# Remote_sensor.net
KiCad netlist of a schematic drawn in Altium Designer
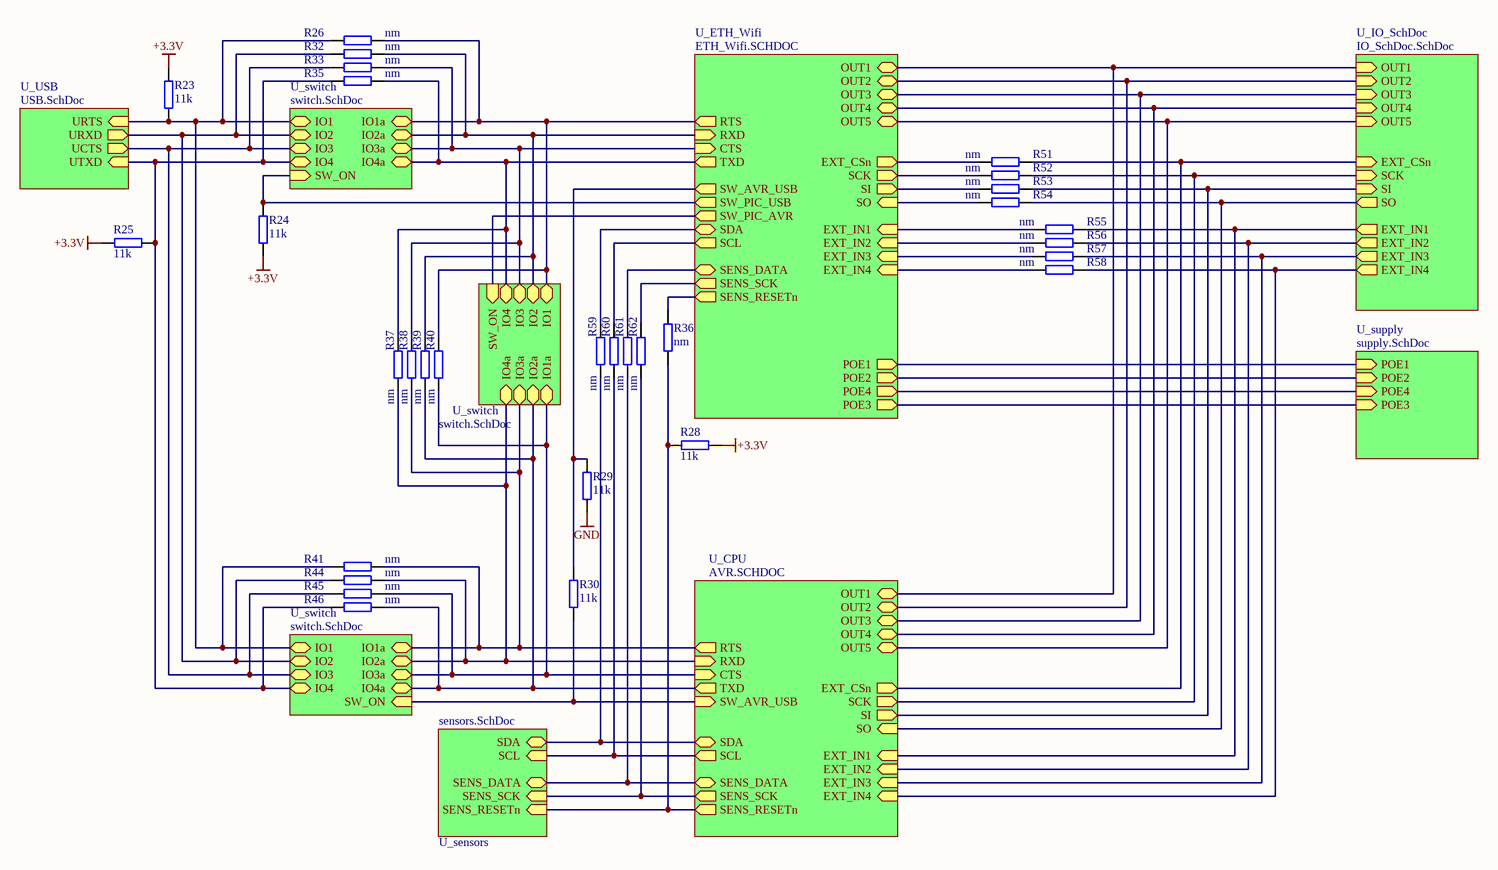
[diagram p0: Remote_sensor.SCHDOC]

(export (version "E")
  (design (tool "Eeschema 10.0.6"))
  (components
    (comp (ref "R23")
      (value "11k")
      (footprint "0603")
      (description "SMD Resistor")
      (libsource (lib "LIBRARY_SCH") (part "RES_SMD"))
    )
    (comp (ref "R24")
      (value "11k")
      (footprint "0603")
      (description "SMD Resistor")
      (libsource (lib "LIBRARY_SCH") (part "RES_SMD"))
    )
    (comp (ref "R25")
      (value "11k")
      (footprint "0603")
      (description "SMD Resistor")
      (libsource (lib "LIBRARY_SCH") (part "RES_SMD"))
    )
    (comp (ref "R26")
      (value "nm")
      (footprint "0603")
      (description "SMD Resistor")
      (libsource (lib "LIBRARY_SCH") (part "RES_SMD"))
    )
    (comp (ref "R28")
      (value "11k")
      (footprint "0603")
      (description "SMD Resistor")
      (libsource (lib "LIBRARY_SCH") (part "RES_SMD"))
    )
    (comp (ref "R29")
      (value "11k")
      (footprint "0603")
      (description "SMD Resistor")
      (libsource (lib "LIBRARY_SCH") (part "RES_SMD"))
    )
    (comp (ref "R30")
      (value "11k")
      (footprint "0603")
      (description "SMD Resistor")
      (libsource (lib "LIBRARY_SCH") (part "RES_SMD"))
    )
    (comp (ref "R32")
      (value "nm")
      (footprint "0603")
      (description "SMD Resistor")
      (libsource (lib "LIBRARY_SCH") (part "RES_SMD"))
    )
    (comp (ref "R33")
      (value "nm")
      (footprint "0603")
      (description "SMD Resistor")
      (libsource (lib "LIBRARY_SCH") (part "RES_SMD"))
    )
    (comp (ref "R35")
      (value "nm")
      (footprint "0603")
      (description "SMD Resistor")
      (libsource (lib "LIBRARY_SCH") (part "RES_SMD"))
    )
    (comp (ref "R36")
      (value "nm")
      (footprint "0603")
      (description "SMD Resistor")
      (libsource (lib "LIBRARY_SCH") (part "RES_SMD"))
    )
    (comp (ref "R37")
      (value "nm")
      (footprint "0603")
      (description "SMD Resistor")
      (libsource (lib "LIBRARY_SCH") (part "RES_SMD"))
    )
    (comp (ref "R38")
      (value "nm")
      (footprint "0603")
      (description "SMD Resistor")
      (libsource (lib "LIBRARY_SCH") (part "RES_SMD"))
    )
    (comp (ref "R39")
      (value "nm")
      (footprint "0603")
      (description "SMD Resistor")
      (libsource (lib "LIBRARY_SCH") (part "RES_SMD"))
    )
    (comp (ref "R40")
      (value "nm")
      (footprint "0603")
      (description "SMD Resistor")
      (libsource (lib "LIBRARY_SCH") (part "RES_SMD"))
    )
    (comp (ref "R41")
      (value "nm")
      (footprint "0603")
      (description "SMD Resistor")
      (libsource (lib "LIBRARY_SCH") (part "RES_SMD"))
    )
    (comp (ref "R44")
      (value "nm")
      (footprint "0603")
      (description "SMD Resistor")
      (libsource (lib "LIBRARY_SCH") (part "RES_SMD"))
    )
    (comp (ref "R45")
      (value "nm")
      (footprint "0603")
      (description "SMD Resistor")
      (libsource (lib "LIBRARY_SCH") (part "RES_SMD"))
    )
    (comp (ref "R46")
      (value "nm")
      (footprint "0603")
      (description "SMD Resistor")
      (libsource (lib "LIBRARY_SCH") (part "RES_SMD"))
    )
    (comp (ref "R51")
      (value "nm")
      (footprint "0603")
      (description "SMD Resistor")
      (libsource (lib "LIBRARY_SCH") (part "RES_SMD"))
    )
    (comp (ref "R52")
      (value "nm")
      (footprint "0603")
      (description "SMD Resistor")
      (libsource (lib "LIBRARY_SCH") (part "RES_SMD"))
    )
    (comp (ref "R53")
      (value "nm")
      (footprint "0603")
      (description "SMD Resistor")
      (libsource (lib "LIBRARY_SCH") (part "RES_SMD"))
    )
    (comp (ref "R54")
      (value "nm")
      (footprint "0603")
      (description "SMD Resistor")
      (libsource (lib "LIBRARY_SCH") (part "RES_SMD"))
    )
    (comp (ref "R55")
      (value "nm")
      (footprint "0603")
      (description "SMD Resistor")
      (libsource (lib "LIBRARY_SCH") (part "RES_SMD"))
    )
    (comp (ref "R56")
      (value "nm")
      (footprint "0603")
      (description "SMD Resistor")
      (libsource (lib "LIBRARY_SCH") (part "RES_SMD"))
    )
    (comp (ref "R57")
      (value "nm")
      (footprint "0603")
      (description "SMD Resistor")
      (libsource (lib "LIBRARY_SCH") (part "RES_SMD"))
    )
    (comp (ref "R58")
      (value "nm")
      (footprint "0603")
      (description "SMD Resistor")
      (libsource (lib "LIBRARY_SCH") (part "RES_SMD"))
    )
    (comp (ref "R59")
      (value "nm")
      (footprint "0603")
      (description "SMD Resistor")
      (libsource (lib "LIBRARY_SCH") (part "RES_SMD"))
    )
    (comp (ref "R60")
      (value "nm")
      (footprint "0603")
      (description "SMD Resistor")
      (libsource (lib "LIBRARY_SCH") (part "RES_SMD"))
    )
    (comp (ref "R61")
      (value "nm")
      (footprint "0603")
      (description "SMD Resistor")
      (libsource (lib "LIBRARY_SCH") (part "RES_SMD"))
    )
    (comp (ref "R62")
      (value "nm")
      (footprint "0603")
      (description "SMD Resistor")
      (libsource (lib "LIBRARY_SCH") (part "RES_SMD"))
    )
  )
  (nets
    (net (code "1") (name "+3.3V") (class "Default")
      (node (ref "R23") (pin "2") (pinfunction "2_2") (pintype "passive"))
      (node (ref "R24") (pin "1") (pinfunction "1_1") (pintype "passive"))
      (node (ref "R25") (pin "2") (pinfunction "2_2") (pintype "passive"))
      (node (ref "R28") (pin "1") (pinfunction "1_1") (pintype "passive"))
    )
    (net (code "2") (name "/CTS") (class "Default")
      (node (ref "R40") (pin "2") (pinfunction "2_2") (pintype "passive"))
      (node (ref "R45") (pin "1") (pinfunction "1_1") (pintype "passive"))
    )
    (net (code "3") (name "/CTS_1") (class "Default")
      (node (ref "R33") (pin "1") (pinfunction "1_1") (pintype "passive"))
      (node (ref "R38") (pin "1") (pinfunction "1_1") (pintype "passive"))
    )
    (net (code "4") (name "/EXT_CSn") (class "Default")
      (node (ref "R51") (pin "2") (pinfunction "2_2") (pintype "passive"))
    )
    (net (code "5") (name "/EXT_CSn_1") (class "Default")
      (node (ref "R51") (pin "1") (pinfunction "1_1") (pintype "passive"))
    )
    (net (code "6") (name "/EXT_IN1") (class "Default")
      (node (ref "R55") (pin "2") (pinfunction "2_2") (pintype "passive"))
    )
    (net (code "7") (name "/EXT_IN1_1") (class "Default")
      (node (ref "R55") (pin "1") (pinfunction "1_1") (pintype "passive"))
    )
    (net (code "8") (name "/EXT_IN2") (class "Default")
      (node (ref "R56") (pin "2") (pinfunction "2_2") (pintype "passive"))
    )
    (net (code "9") (name "/EXT_IN2_1") (class "Default")
      (node (ref "R56") (pin "1") (pinfunction "1_1") (pintype "passive"))
    )
    (net (code "10") (name "/EXT_IN3") (class "Default")
      (node (ref "R57") (pin "2") (pinfunction "2_2") (pintype "passive"))
    )
    (net (code "11") (name "/EXT_IN3_1") (class "Default")
      (node (ref "R57") (pin "1") (pinfunction "1_1") (pintype "passive"))
    )
    (net (code "12") (name "/EXT_IN4") (class "Default")
      (node (ref "R58") (pin "2") (pinfunction "2_2") (pintype "passive"))
    )
    (net (code "13") (name "/EXT_IN4_1") (class "Default")
      (node (ref "R58") (pin "1") (pinfunction "1_1") (pintype "passive"))
    )
    (net (code "14") (name "/IO1") (class "Default")
      (node (ref "R23") (pin "1") (pinfunction "1_1") (pintype "passive"))
      (node (ref "R26") (pin "2") (pinfunction "2_2") (pintype "passive"))
      (node (ref "R41") (pin "2") (pinfunction "2_2") (pintype "passive"))
    )
    (net (code "15") (name "/IO2") (class "Default")
      (node (ref "R32") (pin "1") (pinfunction "1_1") (pintype "passive"))
      (node (ref "R39") (pin "1") (pinfunction "1_1") (pintype "passive"))
    )
    (net (code "16") (name "/IO2a") (class "Default")
      (node (ref "R37") (pin "2") (pinfunction "2_2") (pintype "passive"))
      (node (ref "R44") (pin "1") (pinfunction "1_1") (pintype "passive"))
    )
    (net (code "17") (name "/IO4") (class "Default")
      (node (ref "R25") (pin "1") (pinfunction "1_1") (pintype "passive"))
      (node (ref "R35") (pin "2") (pinfunction "2_2") (pintype "passive"))
      (node (ref "R46") (pin "2") (pinfunction "2_2") (pintype "passive"))
    )
    (net (code "27") (name "/RTS") (class "Default")
      (node (ref "R38") (pin "2") (pinfunction "2_2") (pintype "passive"))
      (node (ref "R41") (pin "1") (pinfunction "1_1") (pintype "passive"))
    )
    (net (code "28") (name "/RTS_1") (class "Default")
      (node (ref "R26") (pin "1") (pinfunction "1_1") (pintype "passive"))
      (node (ref "R40") (pin "1") (pinfunction "1_1") (pintype "passive"))
    )
    (net (code "29") (name "/SCK") (class "Default")
      (node (ref "R52") (pin "2") (pinfunction "2_2") (pintype "passive"))
    )
    (net (code "30") (name "/SCK_1") (class "Default")
      (node (ref "R52") (pin "1") (pinfunction "1_1") (pintype "passive"))
    )
    (net (code "31") (name "/SCL") (class "Default")
      (node (ref "R60") (pin "1") (pinfunction "1_1") (pintype "passive"))
    )
    (net (code "32") (name "/SCL_1") (class "Default")
      (node (ref "R60") (pin "2") (pinfunction "2_2") (pintype "passive"))
    )
    (net (code "33") (name "/SDA") (class "Default")
      (node (ref "R59") (pin "1") (pinfunction "1_1") (pintype "passive"))
    )
    (net (code "34") (name "/SDA_1") (class "Default")
      (node (ref "R59") (pin "2") (pinfunction "2_2") (pintype "passive"))
    )
    (net (code "35") (name "/SENS_DATA") (class "Default")
      (node (ref "R61") (pin "1") (pinfunction "1_1") (pintype "passive"))
    )
    (net (code "36") (name "/SENS_DATA_1") (class "Default")
      (node (ref "R61") (pin "2") (pinfunction "2_2") (pintype "passive"))
    )
    (net (code "37") (name "/SENS_RESETn") (class "Default")
      (node (ref "R36") (pin "2") (pinfunction "2_2") (pintype "passive"))
    )
    (net (code "38") (name "/SENS_RESETn_1") (class "Default")
      (node (ref "R28") (pin "2") (pinfunction "2_2") (pintype "passive"))
      (node (ref "R36") (pin "1") (pinfunction "1_1") (pintype "passive"))
    )
    (net (code "39") (name "/SENS_SCK") (class "Default")
      (node (ref "R62") (pin "1") (pinfunction "1_1") (pintype "passive"))
    )
    (net (code "40") (name "/SENS_SCK_1") (class "Default")
      (node (ref "R62") (pin "2") (pinfunction "2_2") (pintype "passive"))
    )
    (net (code "41") (name "/SI") (class "Default")
      (node (ref "R53") (pin "2") (pinfunction "2_2") (pintype "passive"))
    )
    (net (code "42") (name "/SI_1") (class "Default")
      (node (ref "R53") (pin "1") (pinfunction "1_1") (pintype "passive"))
    )
    (net (code "43") (name "/SO") (class "Default")
      (node (ref "R54") (pin "2") (pinfunction "2_2") (pintype "passive"))
    )
    (net (code "44") (name "/SO_1") (class "Default")
      (node (ref "R54") (pin "1") (pinfunction "1_1") (pintype "passive"))
    )
    (net (code "45") (name "/SW_AVR_USB") (class "Default")
      (node (ref "R30") (pin "1") (pinfunction "1_1") (pintype "passive"))
    )
    (net (code "46") (name "/SW_AVR_USB_1") (class "Default")
      (node (ref "R29") (pin "2") (pinfunction "2_2") (pintype "passive"))
      (node (ref "R30") (pin "2") (pinfunction "2_2") (pintype "passive"))
    )
    (net (code "48") (name "/SW_PIC_USB") (class "Default")
      (node (ref "R24") (pin "2") (pinfunction "2_2") (pintype "passive"))
    )
    (net (code "49") (name "/TXD") (class "Default")
      (node (ref "R39") (pin "2") (pinfunction "2_2") (pintype "passive"))
      (node (ref "R46") (pin "1") (pinfunction "1_1") (pintype "passive"))
    )
    (net (code "50") (name "/TXD_1") (class "Default")
      (node (ref "R35") (pin "1") (pinfunction "1_1") (pintype "passive"))
      (node (ref "R37") (pin "1") (pinfunction "1_1") (pintype "passive"))
    )
    (net (code "51") (name "/UCTS") (class "Default")
      (node (ref "R33") (pin "2") (pinfunction "2_2") (pintype "passive"))
      (node (ref "R45") (pin "2") (pinfunction "2_2") (pintype "passive"))
    )
    (net (code "52") (name "/URXD") (class "Default")
      (node (ref "R32") (pin "2") (pinfunction "2_2") (pintype "passive"))
      (node (ref "R44") (pin "2") (pinfunction "2_2") (pintype "passive"))
    )
    (net (code "53") (name "GND") (class "Default")
      (node (ref "R29") (pin "1") (pinfunction "1_1") (pintype "passive"))
    )
  )
)
